# Clock_Buffer.net
KiCad netlist of a schematic drawn in Altium Designer
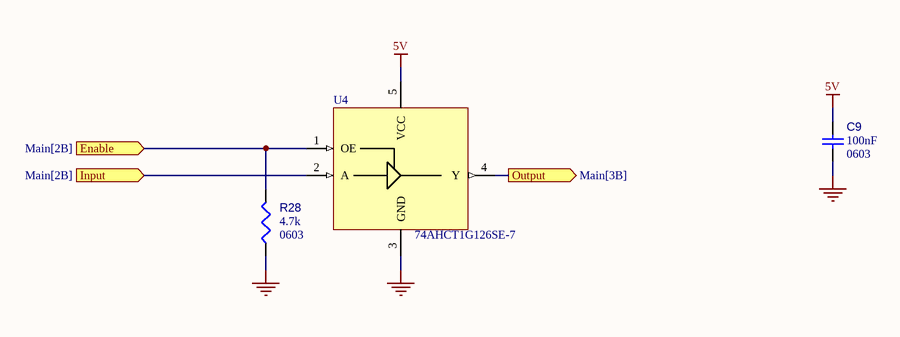
[diagram p0: Clock Buffer.SchDoc]

(export (version "E")
  (design (tool "Eeschema 10.0.6"))
  (components
    (comp (ref "C9")
      (value "100nF")
      (footprint "CAPC1608X90X40NL10T20")
      (description "Chip Capacitor, 100 nF, +/- 10%, 50 V, 0603 (1608 Metric)")
      (fields
        (field (name "TOLERANCE") "10%")
        (field (name "CASE/PACKAGE") "0603")
        (field (name "Comment") "Capacitor 100 nF +/-10% 50 V 0603")
      )
      (libsource (lib "Twill Technology Inc") (part "CAP-NP-2"))
    )
    (comp (ref "R28")
      (value "4.7k")
      (footprint "RESC1608X55X25ML10T15")
      (description "Chip Resistor, 1 KOhm, +/-1%, 0.1 W, -55 to 155 degC, 0603 (1608 Metric)")
      (fields
        (field (name "CASE/PACKAGE") "0603")
        (field (name "POWER") "100mW")
        (field (name "TOLERANCE") "1%")
      )
      (libsource (lib "Twill Technology Inc") (part "RES-2"))
    )
    (comp (ref "U4")
      (value "74AHCT1G126SE-7")
      (footprint "SOT65P210X110-5N")
      (description "74AHC Series 5.5 V Surface Mount Single Buffer Gate w/ 3-ST Output - SOT-353")
      (fields (field (name "MF") "Diodes Inc."))
      (libsource (lib "Twill Technology Inc") (part "74AHCT1G126SE-7"))
    )
  )
  (nets
    (net (code "1") (name "/Enable") (class "Default")
      (node (ref "R28") (pin "2") (pinfunction "2_2") (pintype "passive"))
      (node (ref "U4") (pin "1") (pinfunction "OE_1") (pintype "input"))
    )
    (net (code "2") (name "/Input") (class "Default")
      (node (ref "U4") (pin "2") (pinfunction "A_2") (pintype "input"))
    )
    (net (code "3") (name "/Output") (class "Default")
      (node (ref "U4") (pin "4") (pinfunction "Y_4") (pintype "output"))
    )
    (net (code "4") (name "5V") (class "Default")
      (node (ref "C9") (pin "2") (pinfunction "2_2") (pintype "passive"))
      (node (ref "U4") (pin "5") (pinfunction "VCC_5") (pintype "power_in"))
    )
    (net (code "5") (name "GND") (class "Default")
      (node (ref "C9") (pin "1") (pinfunction "1_1") (pintype "passive"))
      (node (ref "R28") (pin "1") (pinfunction "1_1") (pintype "passive"))
      (node (ref "U4") (pin "3") (pinfunction "GND_3") (pintype "passive"))
    )
  )
)
